# NSE2022_BATTERY_ver0.net
KiCad netlist of a schematic drawn in EAGLE
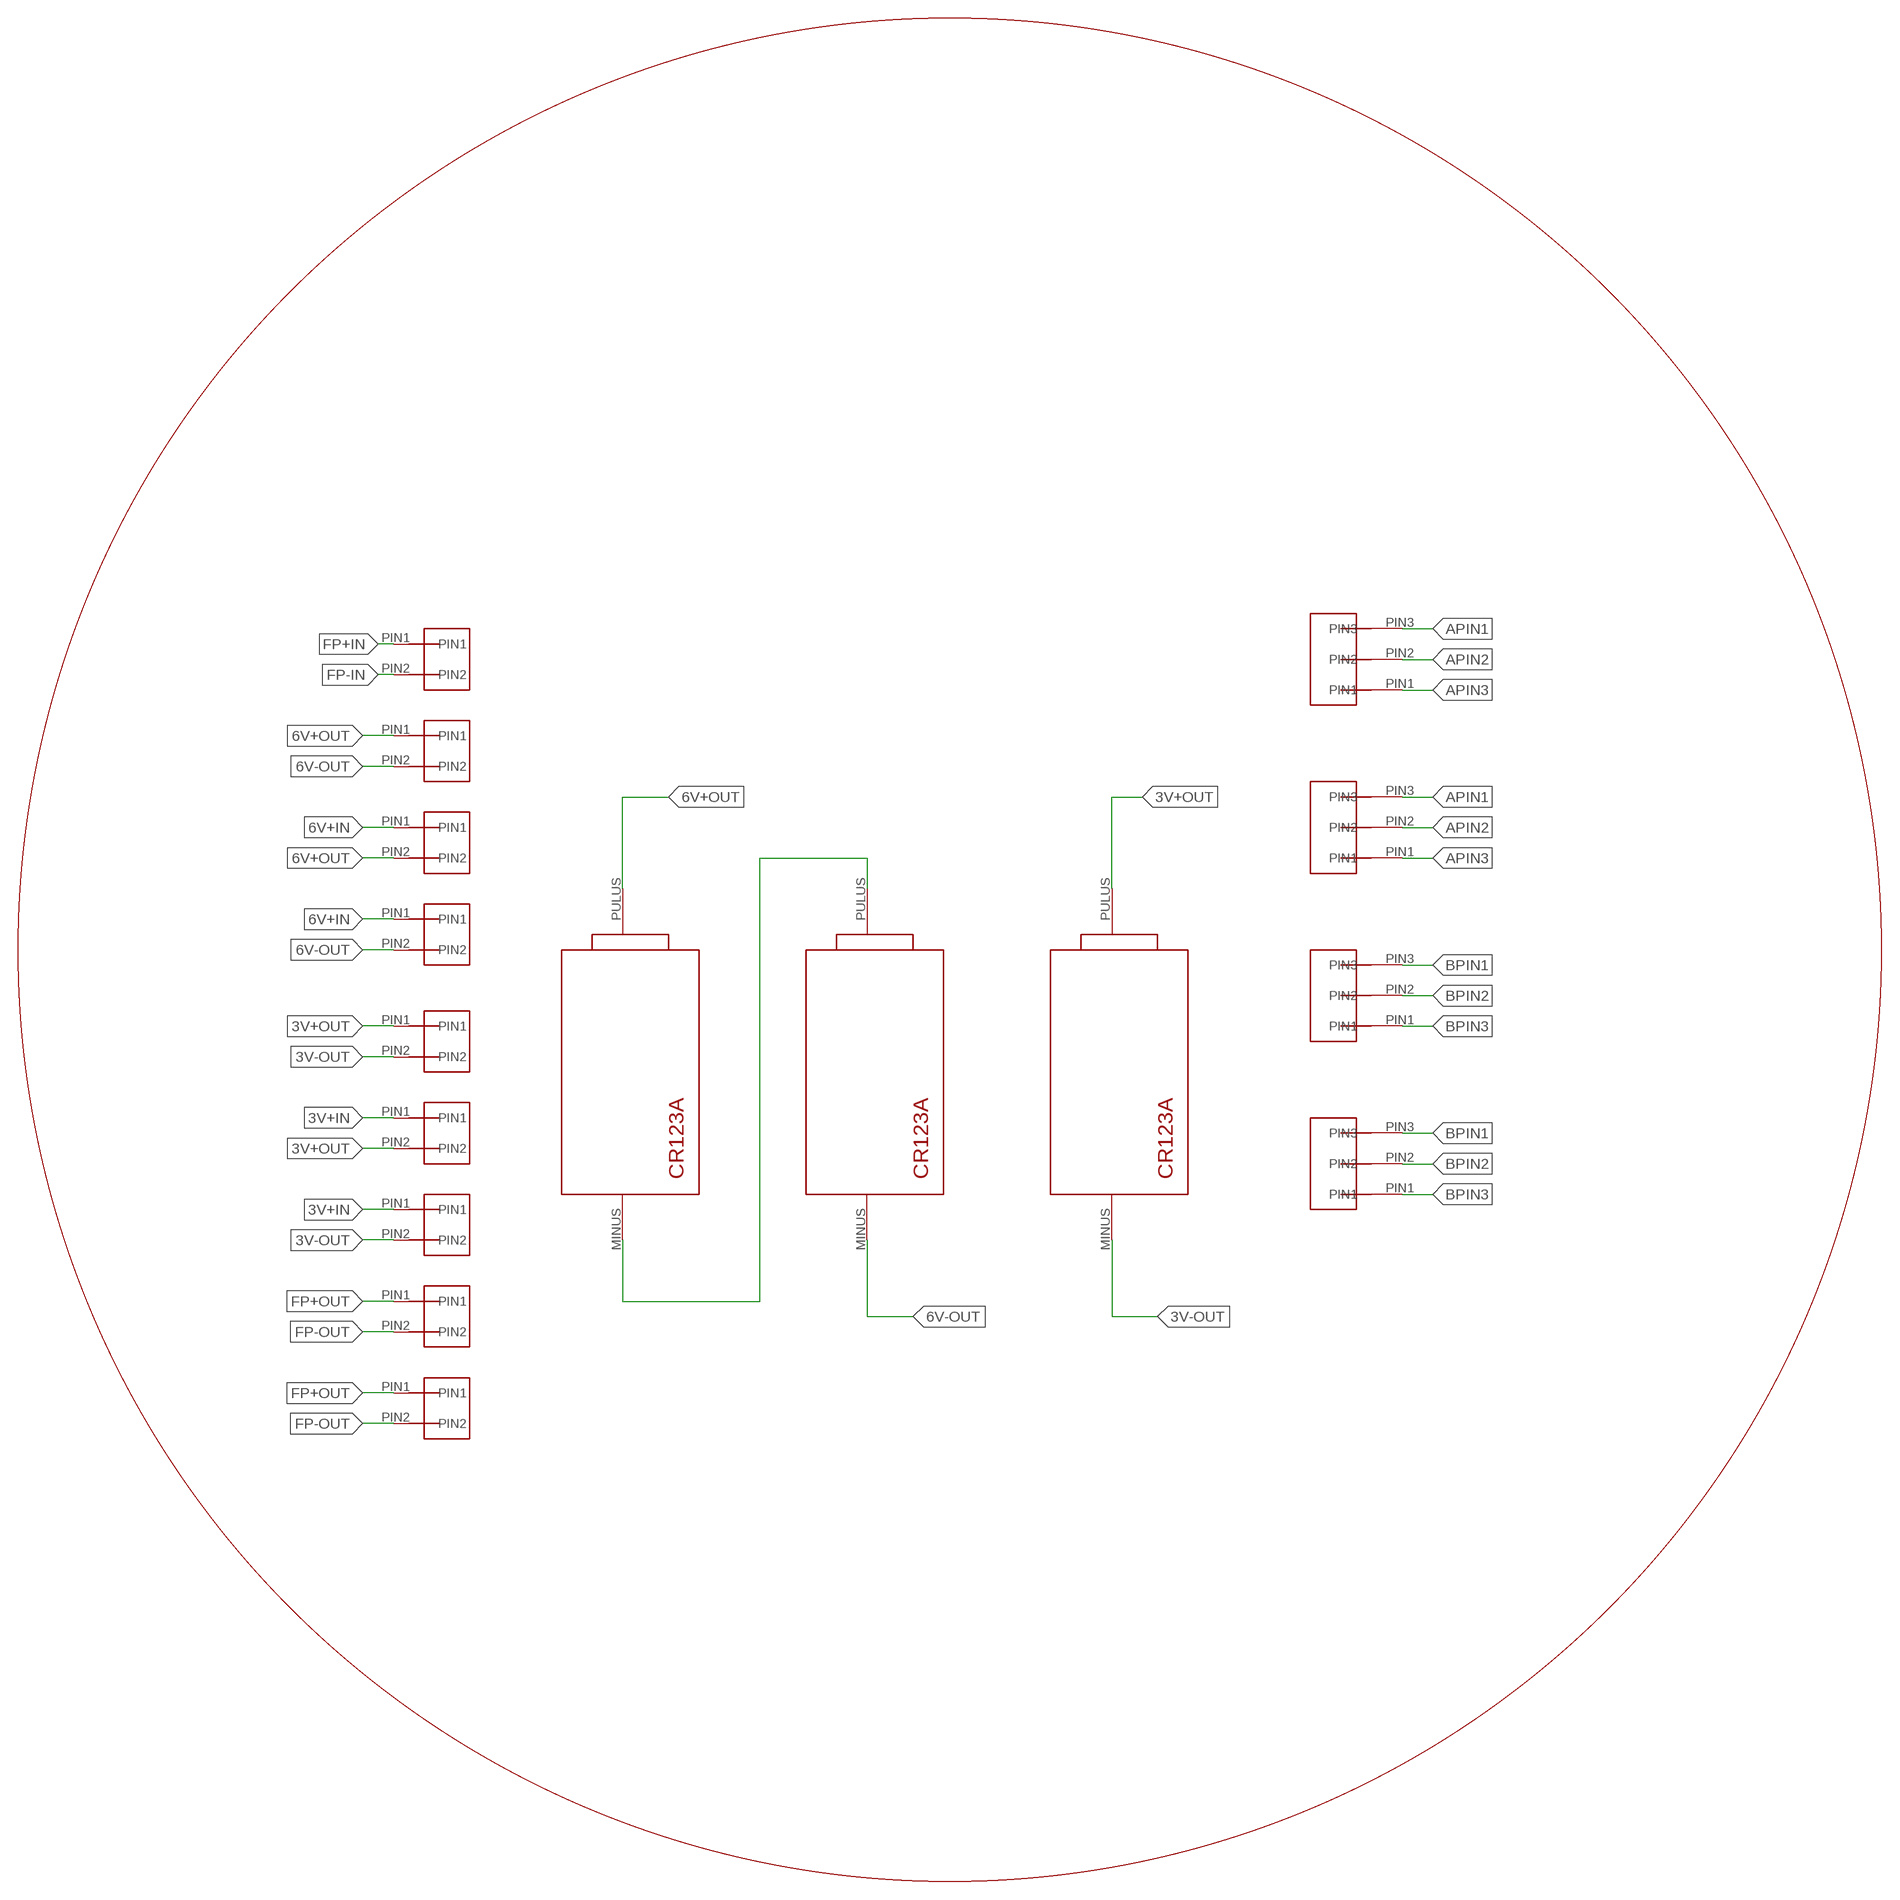
[diagram p0: schematic, sheet 1]

(export (version "E")
  (design (tool "Eeschema 10.0.6"))
  (components
    (comp (ref "U$25")
      (value "CR123A")
      (footprint "eagle-import:CR123A")
      (libsource (lib "eagle-import") (part "CR123A"))
    )
    (comp (ref "U$34")
      (value "CR123A")
      (footprint "eagle-import:CR123A")
      (libsource (lib "eagle-import") (part "CR123A"))
    )
    (comp (ref "U$38")
      (value "CR123A")
      (footprint "eagle-import:CR123A")
      (libsource (lib "eagle-import") (part "CR123A"))
    )
    (comp (ref "U$41")
      (value "2PIN")
      (footprint "eagle-import:2PIN")
      (libsource (lib "eagle-import") (part "2PIN"))
    )
    (comp (ref "U$45")
      (value "2PIN")
      (footprint "eagle-import:2PIN")
      (libsource (lib "eagle-import") (part "2PIN"))
    )
    (comp (ref "U$56")
      (value "2PIN")
      (footprint "eagle-import:2PIN")
      (libsource (lib "eagle-import") (part "2PIN"))
    )
    (comp (ref "U$57")
      (value "2PIN")
      (footprint "eagle-import:2PIN")
      (libsource (lib "eagle-import") (part "2PIN"))
    )
    (comp (ref "U$58")
      (value "2PIN")
      (footprint "eagle-import:2PIN")
      (libsource (lib "eagle-import") (part "2PIN"))
    )
    (comp (ref "U$59")
      (value "3PIN")
      (footprint "eagle-import:3PIN")
      (libsource (lib "eagle-import") (part "3PIN"))
    )
    (comp (ref "U$60")
      (value "3PIN")
      (footprint "eagle-import:3PIN")
      (libsource (lib "eagle-import") (part "3PIN"))
    )
    (comp (ref "U$61")
      (value "3PIN")
      (footprint "eagle-import:3PIN")
      (libsource (lib "eagle-import") (part "3PIN"))
    )
    (comp (ref "U$62")
      (value "3PIN")
      (footprint "eagle-import:3PIN")
      (libsource (lib "eagle-import") (part "3PIN"))
    )
    (comp (ref "U$65")
      (value "2PIN")
      (footprint "eagle-import:2PIN")
      (libsource (lib "eagle-import") (part "2PIN"))
    )
    (comp (ref "U$66")
      (value "2PIN")
      (footprint "eagle-import:2PIN")
      (libsource (lib "eagle-import") (part "2PIN"))
    )
    (comp (ref "U$67")
      (value "2PIN")
      (footprint "eagle-import:2PIN")
      (libsource (lib "eagle-import") (part "2PIN"))
    )
    (comp (ref "U$68")
      (value "2PIN")
      (footprint "eagle-import:2PIN")
      (libsource (lib "eagle-import") (part "2PIN"))
    )
  )
  (nets
    (net (code "1") (name "3V+IN") (class "Default")
      (node (ref "U$56") (pin "PIN1") (pinfunction "PIN1_PIN1") (pintype "bidirectional"))
      (node (ref "U$65") (pin "PIN1") (pinfunction "PIN1_PIN1") (pintype "bidirectional"))
    )
    (net (code "2") (name "3V+OUT") (class "Default")
      (node (ref "U$38") (pin "PULUS") (pinfunction "PULAS_PULUS") (pintype "bidirectional"))
      (node (ref "U$45") (pin "PIN1") (pinfunction "PIN1_PIN1") (pintype "bidirectional"))
      (node (ref "U$56") (pin "PIN2") (pinfunction "PIN2_PIN2") (pintype "bidirectional"))
    )
    (net (code "3") (name "3V-OUT") (class "Default")
      (node (ref "U$38") (pin "MINUS") (pinfunction "MINUS_MINUS") (pintype "bidirectional"))
      (node (ref "U$45") (pin "PIN2") (pinfunction "PIN2_PIN2") (pintype "bidirectional"))
      (node (ref "U$65") (pin "PIN2") (pinfunction "PIN2_PIN2") (pintype "bidirectional"))
    )
    (net (code "4") (name "6V+IN") (class "Default")
      (node (ref "U$67") (pin "PIN1") (pinfunction "PIN1_PIN1") (pintype "bidirectional"))
      (node (ref "U$68") (pin "PIN1") (pinfunction "PIN1_PIN1") (pintype "bidirectional"))
    )
    (net (code "5") (name "6V+OUT") (class "Default")
      (node (ref "U$25") (pin "PULUS") (pinfunction "PULAS_PULUS") (pintype "bidirectional"))
      (node (ref "U$41") (pin "PIN1") (pinfunction "PIN1_PIN1") (pintype "bidirectional"))
      (node (ref "U$67") (pin "PIN2") (pinfunction "PIN2_PIN2") (pintype "bidirectional"))
    )
    (net (code "6") (name "6V-OUT") (class "Default")
      (node (ref "U$34") (pin "MINUS") (pinfunction "MINUS_MINUS") (pintype "bidirectional"))
      (node (ref "U$41") (pin "PIN2") (pinfunction "PIN2_PIN2") (pintype "bidirectional"))
      (node (ref "U$68") (pin "PIN2") (pinfunction "PIN2_PIN2") (pintype "bidirectional"))
    )
    (net (code "7") (name "APIN1") (class "Default")
      (node (ref "U$59") (pin "PIN3") (pinfunction "PIN3_PIN3") (pintype "bidirectional"))
      (node (ref "U$60") (pin "PIN3") (pinfunction "PIN3_PIN3") (pintype "bidirectional"))
    )
    (net (code "8") (name "APIN2") (class "Default")
      (node (ref "U$59") (pin "PIN2") (pinfunction "PIN2_PIN2") (pintype "bidirectional"))
      (node (ref "U$60") (pin "PIN2") (pinfunction "PIN2_PIN2") (pintype "bidirectional"))
    )
    (net (code "9") (name "APIN3") (class "Default")
      (node (ref "U$59") (pin "PIN1") (pinfunction "PIN1_PIN1") (pintype "bidirectional"))
      (node (ref "U$60") (pin "PIN1") (pinfunction "PIN1_PIN1") (pintype "bidirectional"))
    )
    (net (code "10") (name "BPIN1") (class "Default")
      (node (ref "U$61") (pin "PIN3") (pinfunction "PIN3_PIN3") (pintype "bidirectional"))
      (node (ref "U$62") (pin "PIN3") (pinfunction "PIN3_PIN3") (pintype "bidirectional"))
    )
    (net (code "11") (name "BPIN2") (class "Default")
      (node (ref "U$61") (pin "PIN2") (pinfunction "PIN2_PIN2") (pintype "bidirectional"))
      (node (ref "U$62") (pin "PIN2") (pinfunction "PIN2_PIN2") (pintype "bidirectional"))
    )
    (net (code "12") (name "BPIN3") (class "Default")
      (node (ref "U$61") (pin "PIN1") (pinfunction "PIN1_PIN1") (pintype "bidirectional"))
      (node (ref "U$62") (pin "PIN1") (pinfunction "PIN1_PIN1") (pintype "bidirectional"))
    )
    (net (code "13") (name "FP+IN") (class "Default")
      (node (ref "U$57") (pin "PIN1") (pinfunction "PIN1_PIN1") (pintype "bidirectional"))
    )
    (net (code "14") (name "FP+OUT") (class "Default")
      (node (ref "U$58") (pin "PIN1") (pinfunction "PIN1_PIN1") (pintype "bidirectional"))
      (node (ref "U$66") (pin "PIN1") (pinfunction "PIN1_PIN1") (pintype "bidirectional"))
    )
    (net (code "15") (name "FP-IN") (class "Default")
      (node (ref "U$57") (pin "PIN2") (pinfunction "PIN2_PIN2") (pintype "bidirectional"))
    )
    (net (code "16") (name "FP-OUT") (class "Default")
      (node (ref "U$58") (pin "PIN2") (pinfunction "PIN2_PIN2") (pintype "bidirectional"))
      (node (ref "U$66") (pin "PIN2") (pinfunction "PIN2_PIN2") (pintype "bidirectional"))
    )
    (net (code "17") (name "Net-(U$34-PULAS)") (class "Default")
      (node (ref "U$25") (pin "MINUS") (pinfunction "MINUS_MINUS") (pintype "bidirectional"))
      (node (ref "U$34") (pin "PULUS") (pinfunction "PULAS_PULUS") (pintype "bidirectional"))
    )
  )
)
